# ME433-hw6-schematic.net
KiCad netlist of a schematic drawn in EAGLE
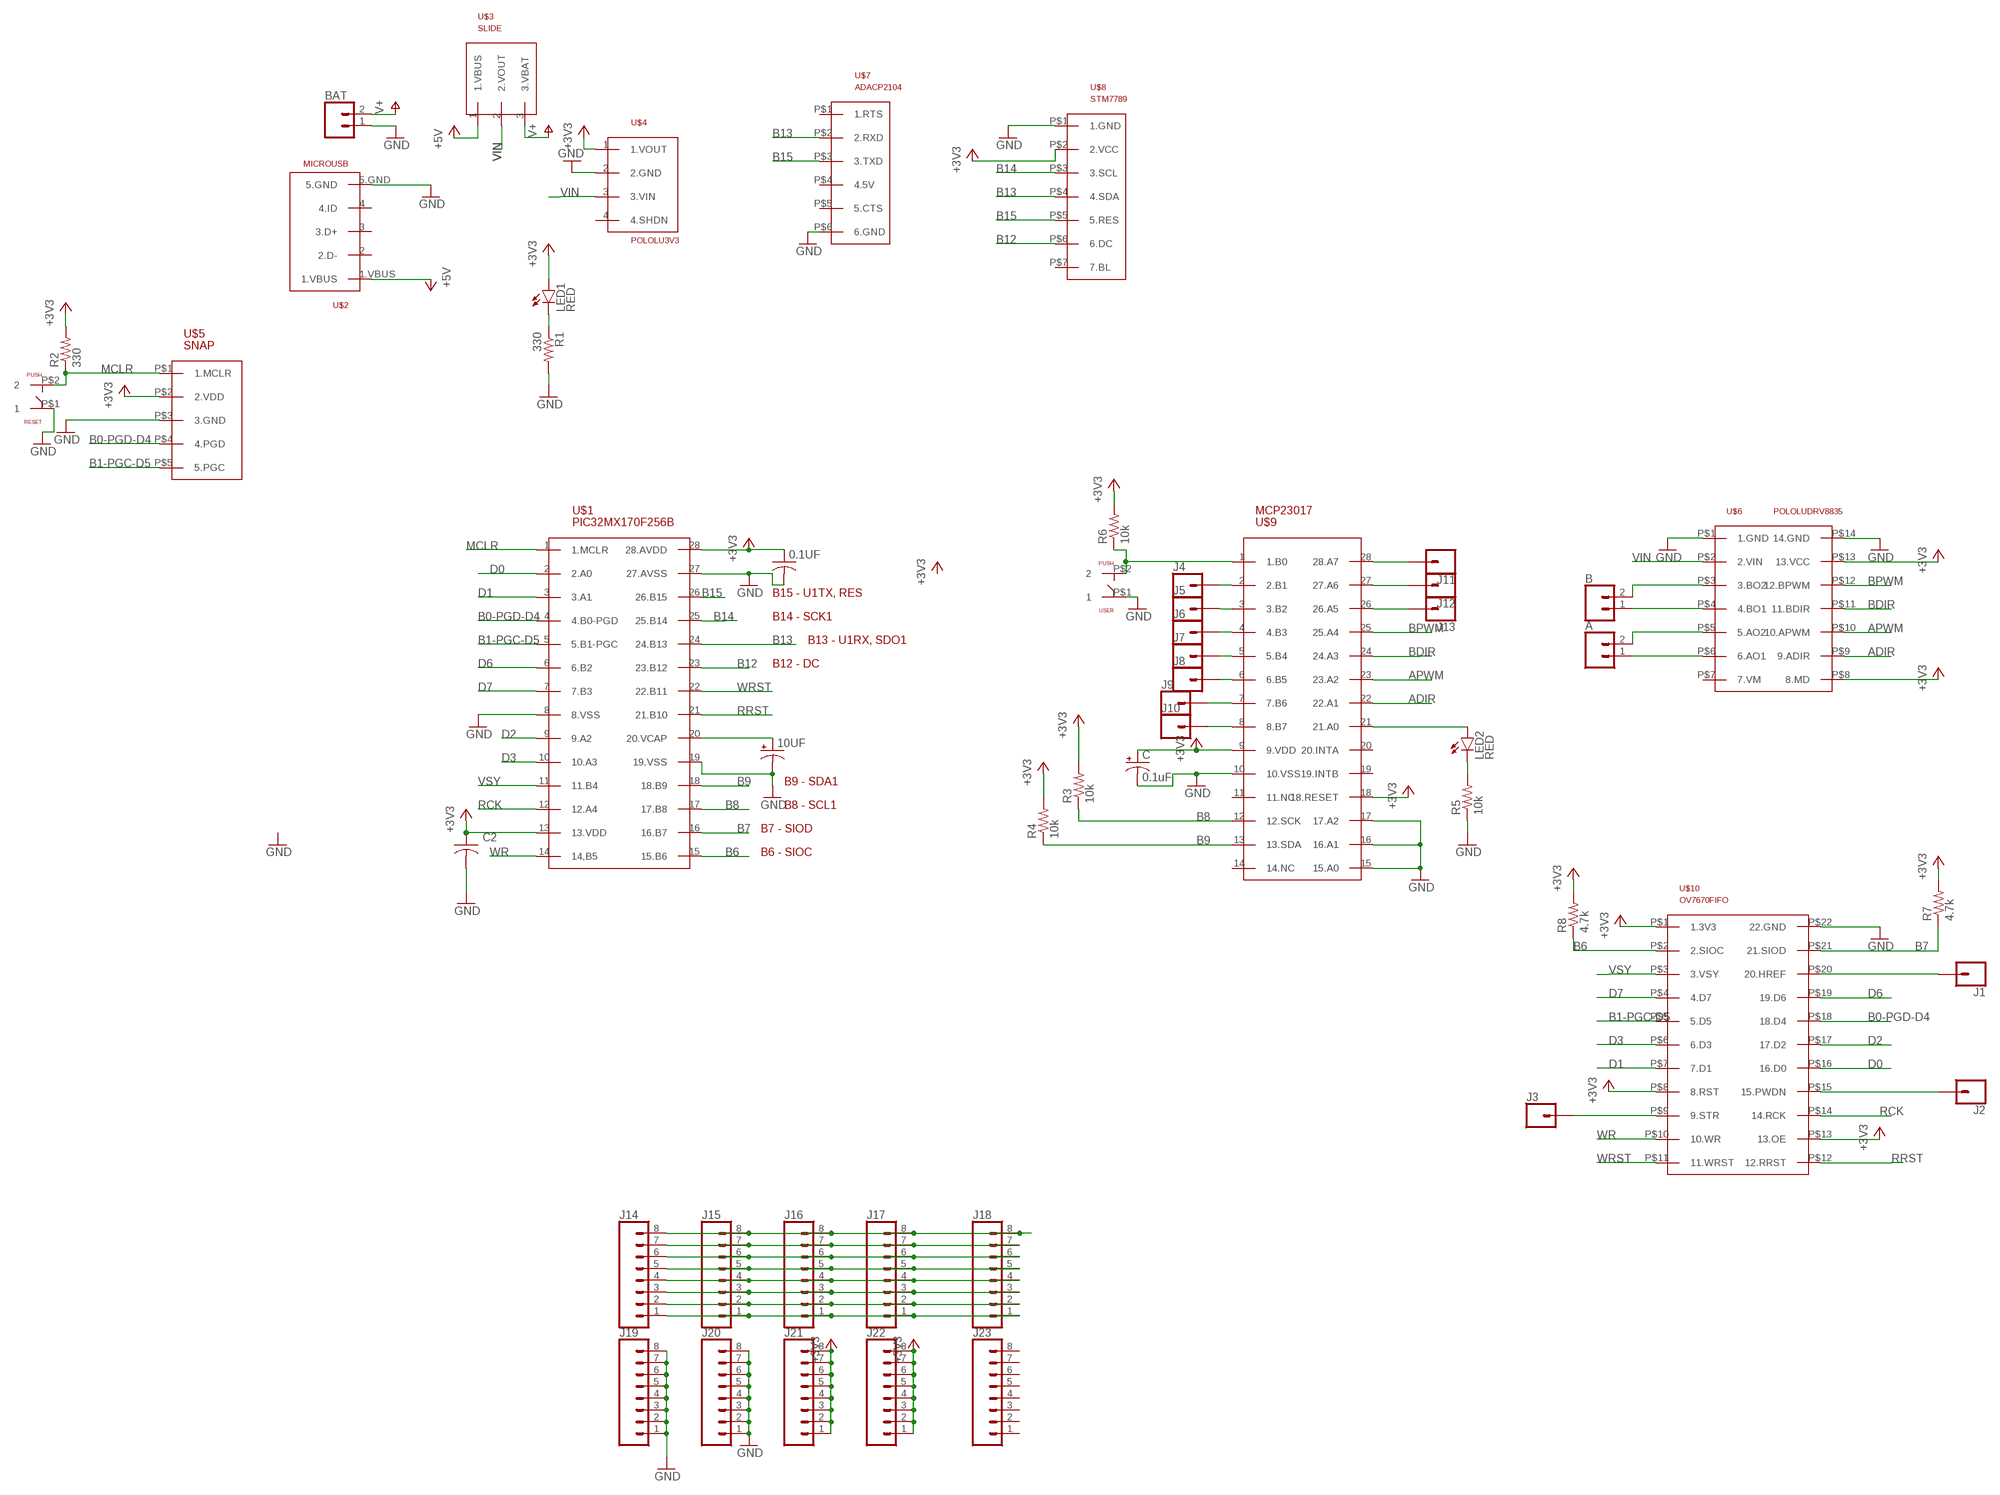
[diagram p0: schematic, sheet 1]

(export (version "E")
  (design (tool "Eeschema 10.0.6"))
  (components
    (comp (ref "0.1UF")
      (value "C-US025-030X050")
      (footprint "eagle-import:C025-030X050")
      (libsource (lib "eagle-import") (part "C-US025-030X050"))
    )
    (comp (ref "10UF")
      (value "CPOL-USB45181B")
      (footprint "eagle-import:B45181B")
      (libsource (lib "eagle-import") (part "CPOL-USB45181B"))
    )
    (comp (ref "A")
      (value "CONN_02")
      (footprint "eagle-import:1X02")
      (libsource (lib "eagle-import") (part "CONN_02"))
    )
    (comp (ref "B")
      (value "CONN_02")
      (footprint "eagle-import:1X02")
      (libsource (lib "eagle-import") (part "CONN_02"))
    )
    (comp (ref "BAT")
      (value "CONN_02")
      (footprint "eagle-import:1X02")
      (libsource (lib "eagle-import") (part "CONN_02"))
    )
    (comp (ref "C")
      (value "0.1uF")
      (footprint "eagle-import:B45181B")
      (libsource (lib "eagle-import") (part "CPOL-USB45181B"))
    )
    (comp (ref "C2")
      (value "C-US025-030X050")
      (footprint "eagle-import:C025-030X050")
      (libsource (lib "eagle-import") (part "C-US025-030X050"))
    )
    (comp (ref "J1")
      (value "CONN_01")
      (footprint "eagle-import:1X01")
      (libsource (lib "eagle-import") (part "CONN_01"))
    )
    (comp (ref "J2")
      (value "CONN_01")
      (footprint "eagle-import:1X01")
      (libsource (lib "eagle-import") (part "CONN_01"))
    )
    (comp (ref "J3")
      (value "CONN_01")
      (footprint "eagle-import:1X01")
      (libsource (lib "eagle-import") (part "CONN_01"))
    )
    (comp (ref "J4")
      (value "CONN_01")
      (footprint "eagle-import:1X01")
      (libsource (lib "eagle-import") (part "CONN_01"))
    )
    (comp (ref "J5")
      (value "CONN_01")
      (footprint "eagle-import:1X01")
      (libsource (lib "eagle-import") (part "CONN_01"))
    )
    (comp (ref "J6")
      (value "CONN_01")
      (footprint "eagle-import:1X01")
      (libsource (lib "eagle-import") (part "CONN_01"))
    )
    (comp (ref "J7")
      (value "CONN_01")
      (footprint "eagle-import:1X01")
      (libsource (lib "eagle-import") (part "CONN_01"))
    )
    (comp (ref "J8")
      (value "CONN_01")
      (footprint "eagle-import:1X01")
      (libsource (lib "eagle-import") (part "CONN_01"))
    )
    (comp (ref "J9")
      (value "CONN_01")
      (footprint "eagle-import:1X01")
      (libsource (lib "eagle-import") (part "CONN_01"))
    )
    (comp (ref "J10")
      (value "CONN_01")
      (footprint "eagle-import:1X01")
      (libsource (lib "eagle-import") (part "CONN_01"))
    )
    (comp (ref "J11")
      (value "CONN_01")
      (footprint "eagle-import:1X01")
      (libsource (lib "eagle-import") (part "CONN_01"))
    )
    (comp (ref "J12")
      (value "CONN_01")
      (footprint "eagle-import:1X01")
      (libsource (lib "eagle-import") (part "CONN_01"))
    )
    (comp (ref "J13")
      (value "CONN_01")
      (footprint "eagle-import:1X01")
      (libsource (lib "eagle-import") (part "CONN_01"))
    )
    (comp (ref "J14")
      (value "CONN_08\"")
      (footprint "eagle-import:1X08")
      (libsource (lib "eagle-import") (part "CONN_08{dblquote}"))
    )
    (comp (ref "J15")
      (value "CONN_08\"")
      (footprint "eagle-import:1X08")
      (libsource (lib "eagle-import") (part "CONN_08{dblquote}"))
    )
    (comp (ref "J16")
      (value "CONN_08\"")
      (footprint "eagle-import:1X08")
      (libsource (lib "eagle-import") (part "CONN_08{dblquote}"))
    )
    (comp (ref "J17")
      (value "CONN_08\"")
      (footprint "eagle-import:1X08")
      (libsource (lib "eagle-import") (part "CONN_08{dblquote}"))
    )
    (comp (ref "J18")
      (value "CONN_08\"")
      (footprint "eagle-import:1X08")
      (libsource (lib "eagle-import") (part "CONN_08{dblquote}"))
    )
    (comp (ref "J19")
      (value "CONN_08\"")
      (footprint "eagle-import:1X08")
      (libsource (lib "eagle-import") (part "CONN_08{dblquote}"))
    )
    (comp (ref "J20")
      (value "CONN_08\"")
      (footprint "eagle-import:1X08")
      (libsource (lib "eagle-import") (part "CONN_08{dblquote}"))
    )
    (comp (ref "J21")
      (value "CONN_08\"")
      (footprint "eagle-import:1X08")
      (libsource (lib "eagle-import") (part "CONN_08{dblquote}"))
    )
    (comp (ref "J22")
      (value "CONN_08\"")
      (footprint "eagle-import:1X08")
      (libsource (lib "eagle-import") (part "CONN_08{dblquote}"))
    )
    (comp (ref "J23")
      (value "CONN_08\"")
      (footprint "eagle-import:1X08")
      (libsource (lib "eagle-import") (part "CONN_08{dblquote}"))
    )
    (comp (ref "LED1")
      (value "RED")
      (footprint "eagle-import:LED3MM")
      (libsource (lib "eagle-import") (part "LED3MM"))
    )
    (comp (ref "LED2")
      (value "RED")
      (footprint "eagle-import:LED3MM")
      (libsource (lib "eagle-import") (part "LED3MM"))
    )
    (comp (ref "R1")
      (value "330")
      (footprint "eagle-import:0207_10")
      (libsource (lib "eagle-import") (part "R-US_0207/10"))
    )
    (comp (ref "R2")
      (value "330")
      (footprint "eagle-import:0207_10")
      (libsource (lib "eagle-import") (part "R-US_0207/10"))
    )
    (comp (ref "R3")
      (value "10k")
      (footprint "eagle-import:0207_10")
      (libsource (lib "eagle-import") (part "R-US_0207/10"))
    )
    (comp (ref "R4")
      (value "10k")
      (footprint "eagle-import:0207_10")
      (libsource (lib "eagle-import") (part "R-US_0207/10"))
    )
    (comp (ref "R5")
      (value "10k")
      (footprint "eagle-import:0207_10")
      (libsource (lib "eagle-import") (part "R-US_0207/10"))
    )
    (comp (ref "R6")
      (value "10k")
      (footprint "eagle-import:0207_10")
      (libsource (lib "eagle-import") (part "R-US_0207/10"))
    )
    (comp (ref "R7")
      (value "4.7k")
      (footprint "eagle-import:0207_10")
      (libsource (lib "eagle-import") (part "R-US_0207/10"))
    )
    (comp (ref "R8")
      (value "4.7k")
      (footprint "eagle-import:0207_10")
      (libsource (lib "eagle-import") (part "R-US_0207/10"))
    )
    (comp (ref "RESET")
      (value "PUSH")
      (footprint "eagle-import:PUSH")
      (libsource (lib "eagle-import") (part "PUSH"))
    )
    (comp (ref "U$1")
      (value "PIC32MX170F256B")
      (footprint "eagle-import:DIL28-3")
      (libsource (lib "eagle-import") (part "PIC32MX170F256B"))
    )
    (comp (ref "U$2")
      (value "MICROUSB")
      (footprint "eagle-import:MICROUSB")
      (libsource (lib "eagle-import") (part "MICROUSB"))
    )
    (comp (ref "U$3")
      (value "SLIDE")
      (footprint "eagle-import:SLIDE")
      (libsource (lib "eagle-import") (part "SLIDE"))
    )
    (comp (ref "U$4")
      (value "POLOLU3V3")
      (footprint "eagle-import:POLOLU3V3")
      (libsource (lib "eagle-import") (part "POLOLU3V3"))
    )
    (comp (ref "U$5")
      (value "SNAP")
      (footprint "eagle-import:SNAP")
      (libsource (lib "eagle-import") (part "SNAP"))
    )
    (comp (ref "U$6")
      (value "POLOLUDRV8835")
      (footprint "eagle-import:POLOLUDRV8835")
      (libsource (lib "eagle-import") (part "POLOLUDRV8835"))
    )
    (comp (ref "U$7")
      (value "ADACP2104")
      (footprint "eagle-import:ADACP2104")
      (libsource (lib "eagle-import") (part "ADACP2104"))
    )
    (comp (ref "U$8")
      (value "STM7789")
      (footprint "eagle-import:STM7789")
      (libsource (lib "eagle-import") (part "STM7789"))
    )
    (comp (ref "U$9")
      (value "MCP23017")
      (footprint "eagle-import:MCP23017")
      (libsource (lib "eagle-import") (part "MCP23017"))
    )
    (comp (ref "U$10")
      (value "OV7670FIFO")
      (footprint "eagle-import:OV7670FIFO")
      (libsource (lib "eagle-import") (part "OV7670FIFO"))
    )
    (comp (ref "USER")
      (value "PUSH")
      (footprint "eagle-import:PUSH")
      (libsource (lib "eagle-import") (part "PUSH"))
    )
  )
  (nets
    (net (code "1") (name "+3V3") (class "Default")
      (node (ref "0.1UF") (pin "1") (pinfunction "1_1") (pintype "passive"))
      (node (ref "C") (pin "+") (pinfunction "+_+") (pintype "passive"))
      (node (ref "C2") (pin "1") (pinfunction "1_1") (pintype "passive"))
      (node (ref "J21") (pin "1") (pinfunction "1_1") (pintype "passive"))
      (node (ref "J21") (pin "2") (pinfunction "2_2") (pintype "passive"))
      (node (ref "J21") (pin "3") (pinfunction "3_3") (pintype "passive"))
      (node (ref "J21") (pin "4") (pinfunction "4_4") (pintype "passive"))
      (node (ref "J21") (pin "5") (pinfunction "5_5") (pintype "passive"))
      (node (ref "J21") (pin "6") (pinfunction "6_6") (pintype "passive"))
      (node (ref "J21") (pin "7") (pinfunction "7_7") (pintype "passive"))
      (node (ref "J21") (pin "8") (pinfunction "8_8") (pintype "passive"))
      (node (ref "J22") (pin "1") (pinfunction "1_1") (pintype "passive"))
      (node (ref "J22") (pin "2") (pinfunction "2_2") (pintype "passive"))
      (node (ref "J22") (pin "3") (pinfunction "3_3") (pintype "passive"))
      (node (ref "J22") (pin "4") (pinfunction "4_4") (pintype "passive"))
      (node (ref "J22") (pin "5") (pinfunction "5_5") (pintype "passive"))
      (node (ref "J22") (pin "6") (pinfunction "6_6") (pintype "passive"))
      (node (ref "J22") (pin "7") (pinfunction "7_7") (pintype "passive"))
      (node (ref "J22") (pin "8") (pinfunction "8_8") (pintype "passive"))
      (node (ref "LED1") (pin "A") (pinfunction "A_A") (pintype "passive"))
      (node (ref "R2") (pin "2") (pinfunction "2_2") (pintype "passive"))
      (node (ref "R3") (pin "2") (pinfunction "2_2") (pintype "passive"))
      (node (ref "R4") (pin "2") (pinfunction "2_2") (pintype "passive"))
      (node (ref "R6") (pin "2") (pinfunction "2_2") (pintype "passive"))
      (node (ref "R7") (pin "2") (pinfunction "2_2") (pintype "passive"))
      (node (ref "R8") (pin "2") (pinfunction "2_2") (pintype "passive"))
      (node (ref "U$1") (pin "13") (pinfunction "13.VDD_13") (pintype "bidirectional"))
      (node (ref "U$1") (pin "28") (pinfunction "28.AVDD_28") (pintype "bidirectional"))
      (node (ref "U$10") (pin "P$1") (pinfunction "1.3V3_P$1") (pintype "bidirectional"))
      (node (ref "U$10") (pin "P$13") (pinfunction "13.OE_P$13") (pintype "bidirectional"))
      (node (ref "U$10") (pin "P$8") (pinfunction "8.RST_P$8") (pintype "bidirectional"))
      (node (ref "U$4") (pin "1") (pinfunction "1.VOUT_1") (pintype "bidirectional"))
      (node (ref "U$5") (pin "P$2") (pinfunction "2.VDD_P$2") (pintype "bidirectional"))
      (node (ref "U$6") (pin "P$13") (pinfunction "13.VCC_P$13") (pintype "bidirectional"))
      (node (ref "U$6") (pin "P$8") (pinfunction "8.MD_P$8") (pintype "bidirectional"))
      (node (ref "U$8") (pin "P$2") (pinfunction "2.VCC_P$2") (pintype "bidirectional"))
      (node (ref "U$9") (pin "18") (pinfunction "18.RESET_18") (pintype "bidirectional"))
      (node (ref "U$9") (pin "9") (pinfunction "9.VDD_9") (pintype "bidirectional"))
    )
    (net (code "2") (name "+5V") (class "Default")
      (node (ref "U$2") (pin "1.VBUS") (pinfunction "1.VBUS_1.VBUS") (pintype "bidirectional"))
      (node (ref "U$3") (pin "1") (pinfunction "1.VBUS_1") (pintype "bidirectional"))
    )
    (net (code "3") (name "/ADIR") (class "Default")
      (node (ref "U$6") (pin "P$9") (pinfunction "9.ADIR_P$9") (pintype "bidirectional"))
      (node (ref "U$9") (pin "22") (pinfunction "22.A1_22") (pintype "bidirectional"))
    )
    (net (code "4") (name "/APWM") (class "Default")
      (node (ref "U$6") (pin "P$10") (pinfunction "10.APWM_P$10") (pintype "bidirectional"))
      (node (ref "U$9") (pin "23") (pinfunction "23.A2_23") (pintype "bidirectional"))
    )
    (net (code "5") (name "/B0-PGD-D4") (class "Default")
      (node (ref "U$1") (pin "4") (pinfunction "4.B0-PGD_4") (pintype "bidirectional"))
      (node (ref "U$10") (pin "P$18") (pinfunction "18.D4_P$18") (pintype "bidirectional"))
      (node (ref "U$5") (pin "P$4") (pinfunction "4.PGD_P$4") (pintype "bidirectional"))
    )
    (net (code "6") (name "/B1-PGC-D5") (class "Default")
      (node (ref "U$1") (pin "5") (pinfunction "5.B1-PGC_5") (pintype "bidirectional"))
      (node (ref "U$10") (pin "P$5") (pinfunction "5.D5_P$5") (pintype "bidirectional"))
      (node (ref "U$5") (pin "P$5") (pinfunction "5.PGC_P$5") (pintype "bidirectional"))
    )
    (net (code "7") (name "/B6") (class "Default")
      (node (ref "R8") (pin "1") (pinfunction "1_1") (pintype "passive"))
      (node (ref "U$1") (pin "15") (pinfunction "15.B6_15") (pintype "bidirectional"))
      (node (ref "U$10") (pin "P$2") (pinfunction "2.SIOC_P$2") (pintype "bidirectional"))
    )
    (net (code "8") (name "/B7") (class "Default")
      (node (ref "R7") (pin "1") (pinfunction "1_1") (pintype "passive"))
      (node (ref "U$1") (pin "16") (pinfunction "16.B7_16") (pintype "bidirectional"))
      (node (ref "U$10") (pin "P$21") (pinfunction "21.SIOD_P$21") (pintype "bidirectional"))
    )
    (net (code "9") (name "/B8") (class "Default")
      (node (ref "R3") (pin "1") (pinfunction "1_1") (pintype "passive"))
      (node (ref "U$1") (pin "17") (pinfunction "17.B8_17") (pintype "bidirectional"))
      (node (ref "U$9") (pin "12") (pinfunction "12.SCK_12") (pintype "bidirectional"))
    )
    (net (code "10") (name "/B9") (class "Default")
      (node (ref "R4") (pin "1") (pinfunction "1_1") (pintype "passive"))
      (node (ref "U$1") (pin "18") (pinfunction "18.B9_18") (pintype "bidirectional"))
      (node (ref "U$9") (pin "13") (pinfunction "13.SDA_13") (pintype "bidirectional"))
    )
    (net (code "11") (name "/B12") (class "Default")
      (node (ref "U$1") (pin "23") (pinfunction "23.B12_23") (pintype "bidirectional"))
      (node (ref "U$8") (pin "P$6") (pinfunction "6.DC_P$6") (pintype "bidirectional"))
    )
    (net (code "12") (name "/B13") (class "Default")
      (node (ref "U$1") (pin "24") (pinfunction "24.B13_24") (pintype "bidirectional"))
      (node (ref "U$7") (pin "P$2") (pinfunction "2.RXD_P$2") (pintype "bidirectional"))
      (node (ref "U$8") (pin "P$4") (pinfunction "4.SDA_P$4") (pintype "bidirectional"))
    )
    (net (code "13") (name "/B14") (class "Default")
      (node (ref "U$1") (pin "25") (pinfunction "25.B14_25") (pintype "bidirectional"))
      (node (ref "U$8") (pin "P$3") (pinfunction "3.SCL_P$3") (pintype "bidirectional"))
    )
    (net (code "14") (name "/B15") (class "Default")
      (node (ref "U$1") (pin "26") (pinfunction "26.B15_26") (pintype "bidirectional"))
      (node (ref "U$7") (pin "P$3") (pinfunction "3.TXD_P$3") (pintype "bidirectional"))
      (node (ref "U$8") (pin "P$5") (pinfunction "5.RES_P$5") (pintype "bidirectional"))
    )
    (net (code "15") (name "/BDIR") (class "Default")
      (node (ref "U$6") (pin "P$11") (pinfunction "11.BDIR_P$11") (pintype "bidirectional"))
      (node (ref "U$9") (pin "24") (pinfunction "24.A3_24") (pintype "bidirectional"))
    )
    (net (code "16") (name "/BPWM") (class "Default")
      (node (ref "U$6") (pin "P$12") (pinfunction "12.BPWM_P$12") (pintype "bidirectional"))
      (node (ref "U$9") (pin "25") (pinfunction "25.A4_25") (pintype "bidirectional"))
    )
    (net (code "17") (name "/D0") (class "Default")
      (node (ref "U$1") (pin "2") (pinfunction "2.A0_2") (pintype "bidirectional"))
      (node (ref "U$10") (pin "P$16") (pinfunction "16.D0_P$16") (pintype "bidirectional"))
    )
    (net (code "18") (name "/D1") (class "Default")
      (node (ref "U$1") (pin "3") (pinfunction "3.A1_3") (pintype "bidirectional"))
      (node (ref "U$10") (pin "P$7") (pinfunction "7.D1_P$7") (pintype "bidirectional"))
    )
    (net (code "19") (name "/D2") (class "Default")
      (node (ref "U$1") (pin "9") (pinfunction "9.A2_9") (pintype "bidirectional"))
      (node (ref "U$10") (pin "P$17") (pinfunction "17.D2_P$17") (pintype "bidirectional"))
    )
    (net (code "20") (name "/D3") (class "Default")
      (node (ref "U$1") (pin "10") (pinfunction "10.A3_10") (pintype "bidirectional"))
      (node (ref "U$10") (pin "P$6") (pinfunction "6.D3_P$6") (pintype "bidirectional"))
    )
    (net (code "21") (name "/D6") (class "Default")
      (node (ref "U$1") (pin "6") (pinfunction "6.B2_6") (pintype "bidirectional"))
      (node (ref "U$10") (pin "P$19") (pinfunction "19.D6_P$19") (pintype "bidirectional"))
    )
    (net (code "22") (name "/D7") (class "Default")
      (node (ref "U$1") (pin "7") (pinfunction "7.B3_7") (pintype "bidirectional"))
      (node (ref "U$10") (pin "P$4") (pinfunction "4.D7_P$4") (pintype "bidirectional"))
    )
    (net (code "23") (name "/MCLR") (class "Default")
      (node (ref "R2") (pin "1") (pinfunction "1_1") (pintype "passive"))
      (node (ref "RESET") (pin "P$2") (pinfunction "2_P$2") (pintype "bidirectional"))
      (node (ref "U$1") (pin "1") (pinfunction "1.MCLR_1") (pintype "bidirectional"))
      (node (ref "U$5") (pin "P$1") (pinfunction "1.MCLR_P$1") (pintype "bidirectional"))
    )
    (net (code "24") (name "/RCK") (class "Default")
      (node (ref "U$1") (pin "12") (pinfunction "12.A4_12") (pintype "bidirectional"))
      (node (ref "U$10") (pin "P$14") (pinfunction "14.RCK_P$14") (pintype "bidirectional"))
    )
    (net (code "25") (name "/RRST") (class "Default")
      (node (ref "U$1") (pin "21") (pinfunction "21.B10_21") (pintype "bidirectional"))
      (node (ref "U$10") (pin "P$12") (pinfunction "12.RRST_P$12") (pintype "bidirectional"))
    )
    (net (code "26") (name "/VIN") (class "Default")
      (node (ref "U$3") (pin "2") (pinfunction "2.VOUT_2") (pintype "bidirectional"))
      (node (ref "U$4") (pin "3") (pinfunction "3.VIN_3") (pintype "bidirectional"))
      (node (ref "U$6") (pin "P$2") (pinfunction "2.VIN_P$2") (pintype "bidirectional"))
    )
    (net (code "27") (name "/VSY") (class "Default")
      (node (ref "U$1") (pin "11") (pinfunction "11.B4_11") (pintype "bidirectional"))
      (node (ref "U$10") (pin "P$3") (pinfunction "3.VSY_P$3") (pintype "bidirectional"))
    )
    (net (code "28") (name "/WR") (class "Default")
      (node (ref "U$1") (pin "14") (pinfunction "14,B5_14") (pintype "bidirectional"))
      (node (ref "U$10") (pin "P$10") (pinfunction "10.WR_P$10") (pintype "bidirectional"))
    )
    (net (code "29") (name "/WRST") (class "Default")
      (node (ref "U$1") (pin "22") (pinfunction "22.B11_22") (pintype "bidirectional"))
      (node (ref "U$10") (pin "P$11") (pinfunction "11.WRST_P$11") (pintype "bidirectional"))
    )
    (net (code "30") (name "GND") (class "Default")
      (node (ref "0.1UF") (pin "2") (pinfunction "2_2") (pintype "passive"))
      (node (ref "10UF") (pin "-") (pinfunction "-_-") (pintype "passive"))
      (node (ref "BAT") (pin "1") (pinfunction "1_1") (pintype "passive"))
      (node (ref "C") (pin "-") (pinfunction "-_-") (pintype "passive"))
      (node (ref "C2") (pin "2") (pinfunction "2_2") (pintype "passive"))
      (node (ref "J19") (pin "1") (pinfunction "1_1") (pintype "passive"))
      (node (ref "J19") (pin "2") (pinfunction "2_2") (pintype "passive"))
      (node (ref "J19") (pin "3") (pinfunction "3_3") (pintype "passive"))
      (node (ref "J19") (pin "4") (pinfunction "4_4") (pintype "passive"))
      (node (ref "J19") (pin "5") (pinfunction "5_5") (pintype "passive"))
      (node (ref "J19") (pin "6") (pinfunction "6_6") (pintype "passive"))
      (node (ref "J19") (pin "7") (pinfunction "7_7") (pintype "passive"))
      (node (ref "J19") (pin "8") (pinfunction "8_8") (pintype "passive"))
      (node (ref "J20") (pin "1") (pinfunction "1_1") (pintype "passive"))
      (node (ref "J20") (pin "2") (pinfunction "2_2") (pintype "passive"))
      (node (ref "J20") (pin "3") (pinfunction "3_3") (pintype "passive"))
      (node (ref "J20") (pin "4") (pinfunction "4_4") (pintype "passive"))
      (node (ref "J20") (pin "5") (pinfunction "5_5") (pintype "passive"))
      (node (ref "J20") (pin "6") (pinfunction "6_6") (pintype "passive"))
      (node (ref "J20") (pin "7") (pinfunction "7_7") (pintype "passive"))
      (node (ref "J20") (pin "8") (pinfunction "8_8") (pintype "passive"))
      (node (ref "R1") (pin "2") (pinfunction "2_2") (pintype "passive"))
      (node (ref "R5") (pin "1") (pinfunction "1_1") (pintype "passive"))
      (node (ref "RESET") (pin "P$1") (pinfunction "1_P$1") (pintype "bidirectional"))
      (node (ref "U$1") (pin "19") (pinfunction "19.VSS_19") (pintype "bidirectional"))
      (node (ref "U$1") (pin "27") (pinfunction "27.AVSS_27") (pintype "bidirectional"))
      (node (ref "U$1") (pin "8") (pinfunction "8.VSS_8") (pintype "bidirectional"))
      (node (ref "U$10") (pin "P$22") (pinfunction "22.GND_P$22") (pintype "bidirectional"))
      (node (ref "U$2") (pin "5.GND") (pinfunction "5.GND_5.GND") (pintype "bidirectional"))
      (node (ref "U$4") (pin "2") (pinfunction "2.GND_2") (pintype "bidirectional"))
      (node (ref "U$5") (pin "P$3") (pinfunction "3.GND_P$3") (pintype "bidirectional"))
      (node (ref "U$6") (pin "P$1") (pinfunction "1.GND_P$1") (pintype "bidirectional"))
      (node (ref "U$6") (pin "P$14") (pinfunction "14.GND_P$14") (pintype "bidirectional"))
      (node (ref "U$7") (pin "P$6") (pinfunction "6.GND_P$6") (pintype "bidirectional"))
      (node (ref "U$8") (pin "P$1") (pinfunction "1.GND_P$1") (pintype "bidirectional"))
      (node (ref "U$9") (pin "10") (pinfunction "10.VSS_10") (pintype "bidirectional"))
      (node (ref "U$9") (pin "15") (pinfunction "15.A0_15") (pintype "bidirectional"))
      (node (ref "U$9") (pin "16") (pinfunction "16.A1_16") (pintype "bidirectional"))
      (node (ref "U$9") (pin "17") (pinfunction "17.A2_17") (pintype "bidirectional"))
      (node (ref "USER") (pin "P$1") (pinfunction "1_P$1") (pintype "bidirectional"))
    )
    (net (code "31") (name "Net-(J14-Pad1)") (class "Default")
      (node (ref "J14") (pin "1") (pinfunction "1_1") (pintype "passive"))
      (node (ref "J15") (pin "1") (pinfunction "1_1") (pintype "passive"))
      (node (ref "J16") (pin "1") (pinfunction "1_1") (pintype "passive"))
      (node (ref "J17") (pin "1") (pinfunction "1_1") (pintype "passive"))
      (node (ref "J18") (pin "1") (pinfunction "1_1") (pintype "passive"))
    )
    (net (code "32") (name "Net-(J14-Pad2)") (class "Default")
      (node (ref "J14") (pin "2") (pinfunction "2_2") (pintype "passive"))
      (node (ref "J15") (pin "2") (pinfunction "2_2") (pintype "passive"))
      (node (ref "J16") (pin "2") (pinfunction "2_2") (pintype "passive"))
      (node (ref "J17") (pin "2") (pinfunction "2_2") (pintype "passive"))
      (node (ref "J18") (pin "2") (pinfunction "2_2") (pintype "passive"))
    )
    (net (code "33") (name "Net-(J14-Pad3)") (class "Default")
      (node (ref "J14") (pin "3") (pinfunction "3_3") (pintype "passive"))
      (node (ref "J15") (pin "3") (pinfunction "3_3") (pintype "passive"))
      (node (ref "J16") (pin "3") (pinfunction "3_3") (pintype "passive"))
      (node (ref "J17") (pin "3") (pinfunction "3_3") (pintype "passive"))
      (node (ref "J18") (pin "3") (pinfunction "3_3") (pintype "passive"))
    )
    (net (code "34") (name "Net-(J14-Pad4)") (class "Default")
      (node (ref "J14") (pin "4") (pinfunction "4_4") (pintype "passive"))
      (node (ref "J15") (pin "4") (pinfunction "4_4") (pintype "passive"))
      (node (ref "J16") (pin "4") (pinfunction "4_4") (pintype "passive"))
      (node (ref "J17") (pin "4") (pinfunction "4_4") (pintype "passive"))
      (node (ref "J18") (pin "4") (pinfunction "4_4") (pintype "passive"))
    )
    (net (code "35") (name "Net-(J14-Pad5)") (class "Default")
      (node (ref "J14") (pin "5") (pinfunction "5_5") (pintype "passive"))
      (node (ref "J15") (pin "5") (pinfunction "5_5") (pintype "passive"))
      (node (ref "J16") (pin "5") (pinfunction "5_5") (pintype "passive"))
      (node (ref "J17") (pin "5") (pinfunction "5_5") (pintype "passive"))
      (node (ref "J18") (pin "5") (pinfunction "5_5") (pintype "passive"))
    )
    (net (code "36") (name "Net-(J14-Pad6)") (class "Default")
      (node (ref "J14") (pin "6") (pinfunction "6_6") (pintype "passive"))
      (node (ref "J15") (pin "6") (pinfunction "6_6") (pintype "passive"))
      (node (ref "J16") (pin "6") (pinfunction "6_6") (pintype "passive"))
      (node (ref "J17") (pin "6") (pinfunction "6_6") (pintype "passive"))
      (node (ref "J18") (pin "6") (pinfunction "6_6") (pintype "passive"))
    )
    (net (code "37") (name "Net-(J14-Pad7)") (class "Default")
      (node (ref "J14") (pin "7") (pinfunction "7_7") (pintype "passive"))
      (node (ref "J15") (pin "7") (pinfunction "7_7") (pintype "passive"))
      (node (ref "J16") (pin "7") (pinfunction "7_7") (pintype "passive"))
      (node (ref "J17") (pin "7") (pinfunction "7_7") (pintype "passive"))
      (node (ref "J18") (pin "7") (pinfunction "7_7") (pintype "passive"))
    )
    (net (code "38") (name "Net-(J14-Pad8)") (class "Default")
      (node (ref "J14") (pin "8") (pinfunction "8_8") (pintype "passive"))
      (node (ref "J15") (pin "8") (pinfunction "8_8") (pintype "passive"))
      (node (ref "J16") (pin "8") (pinfunction "8_8") (pintype "passive"))
      (node (ref "J17") (pin "8") (pinfunction "8_8") (pintype "passive"))
      (node (ref "J18") (pin "8") (pinfunction "8_8") (pintype "passive"))
    )
    (net (code "39") (name "Net-(LED1-C)") (class "Default")
      (node (ref "LED1") (pin "K") (pinfunction "C_K") (pintype "passive"))
      (node (ref "R1") (pin "1") (pinfunction "1_1") (pintype "passive"))
    )
    (net (code "40") (name "Net-(LED2-C)") (class "Default")
      (node (ref "LED2") (pin "K") (pinfunction "C_K") (pintype "passive"))
      (node (ref "R5") (pin "2") (pinfunction "2_2") (pintype "passive"))
    )
    (net (code "41") (name "Net-(U$1-20.VCAP)") (class "Default")
      (node (ref "10UF") (pin "+") (pinfunction "+_+") (pintype "passive"))
      (node (ref "U$1") (pin "20") (pinfunction "20.VCAP_20") (pintype "bidirectional"))
    )
    (net (code "42") (name "Net-(U$6-3.BO2)") (class "Default")
      (node (ref "B") (pin "2") (pinfunction "2_2") (pintype "passive"))
      (node (ref "U$6") (pin "P$3") (pinfunction "3.BO2_P$3") (pintype "bidirectional"))
    )
    (net (code "43") (name "Net-(U$6-4.BO1)") (class "Default")
      (node (ref "B") (pin "1") (pinfunction "1_1") (pintype "passive"))
      (node (ref "U$6") (pin "P$4") (pinfunction "4.BO1_P$4") (pintype "bidirectional"))
    )
    (net (code "44") (name "Net-(U$6-5.AO2)") (class "Default")
      (node (ref "A") (pin "2") (pinfunction "2_2") (pintype "passive"))
      (node (ref "U$6") (pin "P$5") (pinfunction "5.AO2_P$5") (pintype "bidirectional"))
    )
    (net (code "45") (name "Net-(U$6-6.AO1)") (class "Default")
      (node (ref "A") (pin "1") (pinfunction "1_1") (pintype "passive"))
      (node (ref "U$6") (pin "P$6") (pinfunction "6.AO1_P$6") (pintype "bidirectional"))
    )
    (net (code "46") (name "Net-(U$9-1.B0)") (class "Default")
      (node (ref "R6") (pin "1") (pinfunction "1_1") (pintype "passive"))
      (node (ref "U$9") (pin "1") (pinfunction "1.B0_1") (pintype "bidirectional"))
      (node (ref "USER") (pin "P$2") (pinfunction "2_P$2") (pintype "bidirectional"))
    )
    (net (code "47") (name "Net-(U$9-2.B1)") (class "Default")
      (node (ref "J4") (pin "1") (pinfunction "1_1") (pintype "passive"))
      (node (ref "U$9") (pin "2") (pinfunction "2.B1_2") (pintype "bidirectional"))
    )
    (net (code "48") (name "Net-(U$9-3.B2)") (class "Default")
      (node (ref "J5") (pin "1") (pinfunction "1_1") (pintype "passive"))
      (node (ref "U$9") (pin "3") (pinfunction "3.B2_3") (pintype "bidirectional"))
    )
    (net (code "49") (name "Net-(U$9-4.B3)") (class "Default")
      (node (ref "J6") (pin "1") (pinfunction "1_1") (pintype "passive"))
      (node (ref "U$9") (pin "4") (pinfunction "4.B3_4") (pintype "bidirectional"))
    )
    (net (code "50") (name "Net-(U$9-5.B4)") (class "Default")
      (node (ref "J7") (pin "1") (pinfunction "1_1") (pintype "passive"))
      (node (ref "U$9") (pin "5") (pinfunction "5.B4_5") (pintype "bidirectional"))
    )
    (net (code "51") (name "Net-(U$9-6.B5)") (class "Default")
      (node (ref "J8") (pin "1") (pinfunction "1_1") (pintype "passive"))
      (node (ref "U$9") (pin "6") (pinfunction "6.B5_6") (pintype "bidirectional"))
    )
    (net (code "52") (name "Net-(U$9-7.B6)") (class "Default")
      (node (ref "J9") (pin "1") (pinfunction "1_1") (pintype "passive"))
      (node (ref "U$9") (pin "7") (pinfunction "7.B6_7") (pintype "bidirectional"))
    )
    (net (code "53") (name "Net-(U$9-8.B7)") (class "Default")
      (node (ref "J10") (pin "1") (pinfunction "1_1") (pintype "passive"))
      (node (ref "U$9") (pin "8") (pinfunction "8.B7_8") (pintype "bidirectional"))
    )
    (net (code "54") (name "Net-(U$9-21.A0)") (class "Default")
      (node (ref "LED2") (pin "A") (pinfunction "A_A") (pintype "passive"))
      (node (ref "U$9") (pin "21") (pinfunction "21.A0_21") (pintype "bidirectional"))
    )
    (net (code "55") (name "Net-(U$9-26.A5)") (class "Default")
      (node (ref "J13") (pin "1") (pinfunction "1_1") (pintype "passive"))
      (node (ref "U$9") (pin "26") (pinfunction "26.A5_26") (pintype "bidirectional"))
    )
    (net (code "56") (name "Net-(U$9-27.A6)") (class "Default")
      (node (ref "J12") (pin "1") (pinfunction "1_1") (pintype "passive"))
      (node (ref "U$9") (pin "27") (pinfunction "27.A6_27") (pintype "bidirectional"))
    )
    (net (code "57") (name "Net-(U$9-28.A7)") (class "Default")
      (node (ref "J11") (pin "1") (pinfunction "1_1") (pintype "passive"))
      (node (ref "U$9") (pin "28") (pinfunction "28.A7_28") (pintype "bidirectional"))
    )
    (net (code "58") (name "Net-(U$10-9.STR)") (class "Default")
      (node (ref "J3") (pin "1") (pinfunction "1_1") (pintype "passive"))
      (node (ref "U$10") (pin "P$9") (pinfunction "9.STR_P$9") (pintype "bidirectional"))
    )
    (net (code "59") (name "Net-(U$10-15.PWDN)") (class "Default")
      (node (ref "J2") (pin "1") (pinfunction "1_1") (pintype "passive"))
      (node (ref "U$10") (pin "P$15") (pinfunction "15.PWDN_P$15") (pintype "bidirectional"))
    )
    (net (code "60") (name "Net-(U$10-20.HREF)") (class "Default")
      (node (ref "J1") (pin "1") (pinfunction "1_1") (pintype "passive"))
      (node (ref "U$10") (pin "P$20") (pinfunction "20.HREF_P$20") (pintype "bidirectional"))
    )
    (net (code "61") (name "V+") (class "Default")
      (node (ref "BAT") (pin "2") (pinfunction "2_2") (pintype "passive"))
      (node (ref "U$3") (pin "3") (pinfunction "3.VBAT_3") (pintype "bidirectional"))
    )
    (net (code "62") (name "unconnected-(J23-Pad1)") (class "Default")
      (node (ref "J23") (pin "1") (pinfunction "1_1") (pintype "passive"))
    )
    (net (code "63") (name "unconnected-(J23-Pad2)") (class "Default")
      (node (ref "J23") (pin "2") (pinfunction "2_2") (pintype "passive"))
    )
    (net (code "64") (name "unconnected-(J23-Pad3)") (class "Default")
      (node (ref "J23") (pin "3") (pinfunction "3_3") (pintype "passive"))
    )
    (net (code "65") (name "unconnected-(J23-Pad4)") (class "Default")
      (node (ref "J23") (pin "4") (pinfunction "4_4") (pintype "passive"))
    )
    (net (code "66") (name "unconnected-(J23-Pad5)") (class "Default")
      (node (ref "J23") (pin "5") (pinfunction "5_5") (pintype "passive"))
    )
    (net (code "67") (name "unconnected-(J23-Pad6)") (class "Default")
      (node (ref "J23") (pin "6") (pinfunction "6_6") (pintype "passive"))
    )
    (net (code "68") (name "unconnected-(J23-Pad7)") (class "Default")
      (node (ref "J23") (pin "7") (pinfunction "7_7") (pintype "passive"))
    )
    (net (code "69") (name "unconnected-(J23-Pad8)") (class "Default")
      (node (ref "J23") (pin "8") (pinfunction "8_8") (pintype "passive"))
    )
    (net (code "70") (name "unconnected-(U$2-2.D--Pad2)") (class "Default")
      (node (ref "U$2") (pin "2") (pinfunction "2.D-_2") (pintype "bidirectional"))
    )
    (net (code "71") (name "unconnected-(U$2-3.D+-Pad3)") (class "Default")
      (node (ref "U$2") (pin "3") (pinfunction "3.D+_3") (pintype "bidirectional"))
    )
    (net (code "72") (name "unconnected-(U$2-4.ID-Pad4)") (class "Default")
      (node (ref "U$2") (pin "4") (pinfunction "4.ID_4") (pintype "bidirectional"))
    )
    (net (code "73") (name "unconnected-(U$4-4.SHDN-Pad4)") (class "Default")
      (node (ref "U$4") (pin "4") (pinfunction "4.SHDN_4") (pintype "bidirectional"))
    )
    (net (code "74") (name "unconnected-(U$6-7.VM-PadP$7)") (class "Default")
      (node (ref "U$6") (pin "P$7") (pinfunction "7.VM_P$7") (pintype "bidirectional"))
    )
    (net (code "75") (name "unconnected-(U$7-1.RTS-PadP$1)") (class "Default")
      (node (ref "U$7") (pin "P$1") (pinfunction "1.RTS_P$1") (pintype "bidirectional"))
    )
    (net (code "76") (name "unconnected-(U$7-4.5V-PadP$4)") (class "Default")
      (node (ref "U$7") (pin "P$4") (pinfunction "4.5V_P$4") (pintype "bidirectional"))
    )
    (net (code "77") (name "unconnected-(U$7-5.CTS-PadP$5)") (class "Default")
      (node (ref "U$7") (pin "P$5") (pinfunction "5.CTS_P$5") (pintype "bidirectional"))
    )
    (net (code "78") (name "unconnected-(U$8-7.BL-PadP$7)") (class "Default")
      (node (ref "U$8") (pin "P$7") (pinfunction "7.BL_P$7") (pintype "bidirectional"))
    )
    (net (code "79") (name "unconnected-(U$9-11.NC-Pad11)") (class "Default")
      (node (ref "U$9") (pin "11") (pinfunction "11.NC_11") (pintype "bidirectional"))
    )
    (net (code "80") (name "unconnected-(U$9-14.NC-Pad14)") (class "Default")
      (node (ref "U$9") (pin "14") (pinfunction "14.NC_14") (pintype "bidirectional"))
    )
    (net (code "81") (name "unconnected-(U$9-19.INTB-Pad19)") (class "Default")
      (node (ref "U$9") (pin "19") (pinfunction "19.INTB_19") (pintype "bidirectional"))
    )
    (net (code "82") (name "unconnected-(U$9-20.INTA-Pad20)") (class "Default")
      (node (ref "U$9") (pin "20") (pinfunction "20.INTA_20") (pintype "bidirectional"))
    )
  )
)
